# Brake_Light_Board_1.net
KiCad netlist of a schematic drawn in EAGLE
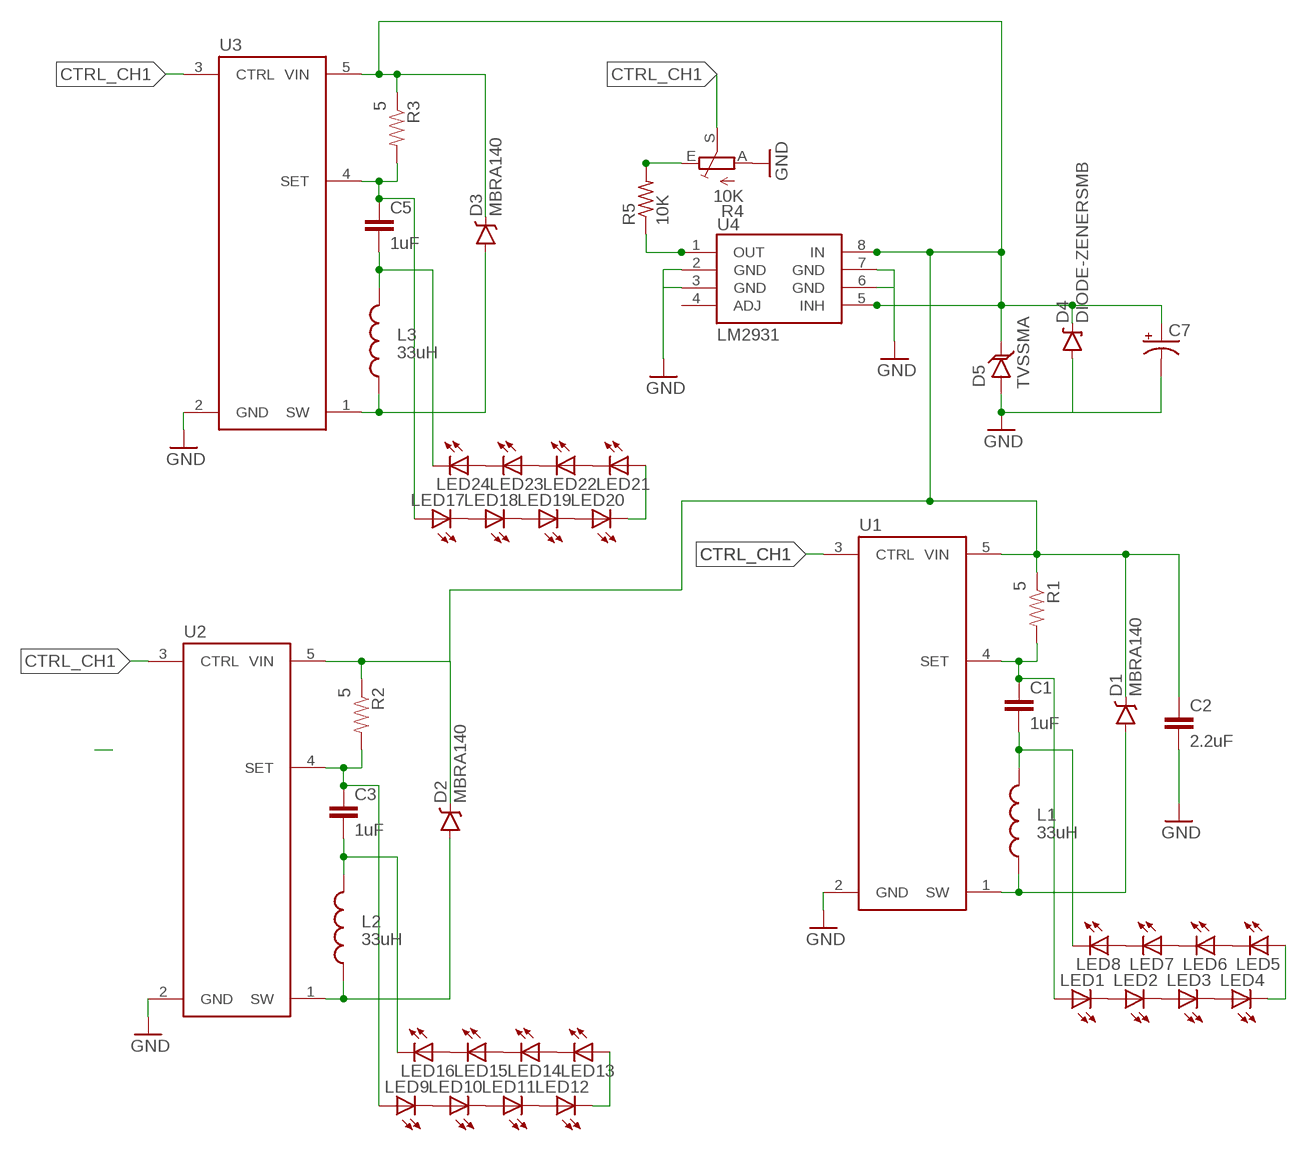
[diagram p0: schematic, sheet 1]

(export (version "E")
  (design (tool "Eeschema 10.0.6"))
  (components
    (comp (ref "C1")
      (value "1uF")
      (footprint "eagle-import:1206")
      (libsource (lib "eagle-import") (part "1.0UF50V10%(1206)"))
    )
    (comp (ref "C2")
      (value "2.2uF")
      (footprint "eagle-import:1206")
      (libsource (lib "eagle-import") (part "2.2UF50V10%(1206)"))
    )
    (comp (ref "C3")
      (value "1uF")
      (footprint "eagle-import:1206")
      (libsource (lib "eagle-import") (part "1.0UF50V10%(1206)"))
    )
    (comp (ref "C5")
      (value "1uF")
      (footprint "eagle-import:1206")
      (libsource (lib "eagle-import") (part "1.0UF50V10%(1206)"))
    )
    (comp (ref "C7")
      (value "CAP_POL6032")
      (footprint "eagle-import:EIA6032")
      (libsource (lib "eagle-import") (part "CAP_POL6032"))
    )
    (comp (ref "D1")
      (value "MBRA140")
      (footprint "eagle-import:SMA-DIODE")
      (libsource (lib "eagle-import") (part "DIODE-SCHOTTKY-MBRA140"))
    )
    (comp (ref "D2")
      (value "MBRA140")
      (footprint "eagle-import:SMA-DIODE")
      (libsource (lib "eagle-import") (part "DIODE-SCHOTTKY-MBRA140"))
    )
    (comp (ref "D3")
      (value "MBRA140")
      (footprint "eagle-import:SMA-DIODE")
      (libsource (lib "eagle-import") (part "DIODE-SCHOTTKY-MBRA140"))
    )
    (comp (ref "D4")
      (value "DIODE-ZENERSMB")
      (footprint "eagle-import:SMB-DIODE")
      (libsource (lib "eagle-import") (part "DIODE-ZENERSMB"))
    )
    (comp (ref "D5")
      (value "TVSSMA")
      (footprint "eagle-import:SMA-DIODE")
      (libsource (lib "eagle-import") (part "TVSSMA"))
    )
    (comp (ref "L1")
      (value "33uH")
      (footprint "eagle-import:SRN6045")
      (libsource (lib "eagle-import") (part "INDUCTORBOURNS_SRN6045"))
    )
    (comp (ref "L2")
      (value "33uH")
      (footprint "eagle-import:SRN6045")
      (libsource (lib "eagle-import") (part "INDUCTORBOURNS_SRN6045"))
    )
    (comp (ref "L3")
      (value "33uH")
      (footprint "eagle-import:SRN6045")
      (libsource (lib "eagle-import") (part "INDUCTORBOURNS_SRN6045"))
    )
    (comp (ref "LED1")
      (value "LED5MM")
      (footprint "eagle-import:LED5MM")
      (libsource (lib "eagle-import") (part "LED5MM"))
    )
    (comp (ref "LED2")
      (value "LED5MM")
      (footprint "eagle-import:LED5MM")
      (libsource (lib "eagle-import") (part "LED5MM"))
    )
    (comp (ref "LED3")
      (value "LED5MM")
      (footprint "eagle-import:LED5MM")
      (libsource (lib "eagle-import") (part "LED5MM"))
    )
    (comp (ref "LED4")
      (value "LED5MM")
      (footprint "eagle-import:LED5MM")
      (libsource (lib "eagle-import") (part "LED5MM"))
    )
    (comp (ref "LED5")
      (value "LED5MM")
      (footprint "eagle-import:LED5MM")
      (libsource (lib "eagle-import") (part "LED5MM"))
    )
    (comp (ref "LED6")
      (value "LED5MM")
      (footprint "eagle-import:LED5MM")
      (libsource (lib "eagle-import") (part "LED5MM"))
    )
    (comp (ref "LED7")
      (value "LED5MM")
      (footprint "eagle-import:LED5MM")
      (libsource (lib "eagle-import") (part "LED5MM"))
    )
    (comp (ref "LED8")
      (value "LED5MM")
      (footprint "eagle-import:LED5MM")
      (libsource (lib "eagle-import") (part "LED5MM"))
    )
    (comp (ref "LED9")
      (value "LED5MM")
      (footprint "eagle-import:LED5MM")
      (libsource (lib "eagle-import") (part "LED5MM"))
    )
    (comp (ref "LED10")
      (value "LED5MM")
      (footprint "eagle-import:LED5MM")
      (libsource (lib "eagle-import") (part "LED5MM"))
    )
    (comp (ref "LED11")
      (value "LED5MM")
      (footprint "eagle-import:LED5MM")
      (libsource (lib "eagle-import") (part "LED5MM"))
    )
    (comp (ref "LED12")
      (value "LED5MM")
      (footprint "eagle-import:LED5MM")
      (libsource (lib "eagle-import") (part "LED5MM"))
    )
    (comp (ref "LED13")
      (value "LED5MM")
      (footprint "eagle-import:LED5MM")
      (libsource (lib "eagle-import") (part "LED5MM"))
    )
    (comp (ref "LED14")
      (value "LED5MM")
      (footprint "eagle-import:LED5MM")
      (libsource (lib "eagle-import") (part "LED5MM"))
    )
    (comp (ref "LED15")
      (value "LED5MM")
      (footprint "eagle-import:LED5MM")
      (libsource (lib "eagle-import") (part "LED5MM"))
    )
    (comp (ref "LED16")
      (value "LED5MM")
      (footprint "eagle-import:LED5MM")
      (libsource (lib "eagle-import") (part "LED5MM"))
    )
    (comp (ref "LED17")
      (value "LED5MM")
      (footprint "eagle-import:LED5MM")
      (libsource (lib "eagle-import") (part "LED5MM"))
    )
    (comp (ref "LED18")
      (value "LED5MM")
      (footprint "eagle-import:LED5MM")
      (libsource (lib "eagle-import") (part "LED5MM"))
    )
    (comp (ref "LED19")
      (value "LED5MM")
      (footprint "eagle-import:LED5MM")
      (libsource (lib "eagle-import") (part "LED5MM"))
    )
    (comp (ref "LED20")
      (value "LED5MM")
      (footprint "eagle-import:LED5MM")
      (libsource (lib "eagle-import") (part "LED5MM"))
    )
    (comp (ref "LED21")
      (value "LED5MM")
      (footprint "eagle-import:LED5MM")
      (libsource (lib "eagle-import") (part "LED5MM"))
    )
    (comp (ref "LED22")
      (value "LED5MM")
      (footprint "eagle-import:LED5MM")
      (libsource (lib "eagle-import") (part "LED5MM"))
    )
    (comp (ref "LED23")
      (value "LED5MM")
      (footprint "eagle-import:LED5MM")
      (libsource (lib "eagle-import") (part "LED5MM"))
    )
    (comp (ref "LED24")
      (value "LED5MM")
      (footprint "eagle-import:LED5MM")
      (libsource (lib "eagle-import") (part "LED5MM"))
    )
    (comp (ref "R1")
      (value "5")
      (footprint "eagle-import:0805")
      (libsource (lib "eagle-import") (part "0.3OHM-1/8W-1%(0805)"))
    )
    (comp (ref "R2")
      (value "5")
      (footprint "eagle-import:0805")
      (libsource (lib "eagle-import") (part "0.3OHM-1/8W-1%(0805)"))
    )
    (comp (ref "R3")
      (value "5")
      (footprint "eagle-import:0805")
      (libsource (lib "eagle-import") (part "0.3OHM-1/8W-1%(0805)"))
    )
    (comp (ref "R4")
      (value "10K")
      (footprint "eagle-import:B25P")
      (libsource (lib "eagle-import") (part "TRIM_EU-B25P"))
    )
    (comp (ref "R5")
      (value "10K")
      (footprint "eagle-import:R0805")
      (libsource (lib "eagle-import") (part "R-US_R0805"))
    )
    (comp (ref "U1")
      (value "AL8805")
      (footprint "eagle-import:SOT23-5")
      (libsource (lib "eagle-import") (part "AL8805"))
    )
    (comp (ref "U2")
      (value "AL8805")
      (footprint "eagle-import:SOT23-5")
      (libsource (lib "eagle-import") (part "AL8805"))
    )
    (comp (ref "U3")
      (value "AL8805")
      (footprint "eagle-import:SOT23-5")
      (libsource (lib "eagle-import") (part "AL8805"))
    )
    (comp (ref "U4")
      (value "LM2931")
      (footprint "eagle-import:SO08")
      (libsource (lib "eagle-import") (part "LM2931"))
    )
  )
  (nets
    (net (code "1") (name "/OUT+1") (class "Default")
      (node (ref "C3") (pin "1") (pinfunction "1_1") (pintype "passive"))
      (node (ref "LED9") (pin "A") (pinfunction "A_A") (pintype "passive"))
      (node (ref "R2") (pin "2") (pinfunction "2_2") (pintype "passive"))
      (node (ref "U2") (pin "4") (pinfunction "SET_4") (pintype "bidirectional"))
    )
    (net (code "2") (name "CTRL_CH1") (class "Default")
      (node (ref "R4") (pin "S") (pinfunction "S_S") (pintype "passive"))
      (node (ref "U1") (pin "3") (pinfunction "CTRL_3") (pintype "bidirectional"))
      (node (ref "U2") (pin "3") (pinfunction "CTRL_3") (pintype "bidirectional"))
      (node (ref "U3") (pin "3") (pinfunction "CTRL_3") (pintype "bidirectional"))
    )
    (net (code "3") (name "GND") (class "Default")
      (node (ref "C2") (pin "2") (pinfunction "2_2") (pintype "passive"))
      (node (ref "C7") (pin "P$2") (pinfunction "-_P$2") (pintype "passive"))
      (node (ref "D4") (pin "A") (pinfunction "A_A") (pintype "passive"))
      (node (ref "D5") (pin "A") (pinfunction "A_A") (pintype "passive"))
      (node (ref "R4") (pin "A") (pinfunction "A_A") (pintype "passive"))
      (node (ref "U1") (pin "2") (pinfunction "GND_2") (pintype "bidirectional"))
      (node (ref "U2") (pin "2") (pinfunction "GND_2") (pintype "bidirectional"))
      (node (ref "U3") (pin "2") (pinfunction "GND_2") (pintype "bidirectional"))
      (node (ref "U4") (pin "2") (pinfunction "GND_2") (pintype "bidirectional"))
      (node (ref "U4") (pin "6") (pinfunction "GND_6") (pintype "bidirectional"))
      (node (ref "U4") (pin "7") (pinfunction "GND_7") (pintype "bidirectional"))
    )
    (net (code "4") (name "Net-(C7-+)") (class "Default")
      (node (ref "C2") (pin "1") (pinfunction "1_1") (pintype "passive"))
      (node (ref "C7") (pin "P$1") (pinfunction "+_P$1") (pintype "passive"))
      (node (ref "D1") (pin "C") (pinfunction "C_C") (pintype "passive"))
      (node (ref "D2") (pin "C") (pinfunction "C_C") (pintype "passive"))
      (node (ref "D3") (pin "C") (pinfunction "C_C") (pintype "passive"))
      (node (ref "D4") (pin "C") (pinfunction "C_C") (pintype "passive"))
      (node (ref "D5") (pin "C") (pinfunction "C_C") (pintype "passive"))
      (node (ref "R1") (pin "1") (pinfunction "1_1") (pintype "passive"))
      (node (ref "R2") (pin "1") (pinfunction "1_1") (pintype "passive"))
      (node (ref "R3") (pin "1") (pinfunction "1_1") (pintype "passive"))
      (node (ref "U1") (pin "5") (pinfunction "VIN_5") (pintype "bidirectional"))
      (node (ref "U2") (pin "5") (pinfunction "VIN_5") (pintype "bidirectional"))
      (node (ref "U3") (pin "5") (pinfunction "VIN_5") (pintype "bidirectional"))
      (node (ref "U4") (pin "5") (pinfunction "INH_5") (pintype "bidirectional"))
      (node (ref "U4") (pin "8") (pinfunction "IN_8") (pintype "bidirectional"))
    )
    (net (code "5") (name "Net-(LED1-C)") (class "Default")
      (node (ref "LED1") (pin "K") (pinfunction "C_K") (pintype "passive"))
      (node (ref "LED2") (pin "A") (pinfunction "A_A") (pintype "passive"))
    )
    (net (code "6") (name "Net-(LED2-C)") (class "Default")
      (node (ref "LED2") (pin "K") (pinfunction "C_K") (pintype "passive"))
      (node (ref "LED3") (pin "A") (pinfunction "A_A") (pintype "passive"))
    )
    (net (code "7") (name "Net-(LED3-C)") (class "Default")
      (node (ref "LED3") (pin "K") (pinfunction "C_K") (pintype "passive"))
      (node (ref "LED4") (pin "A") (pinfunction "A_A") (pintype "passive"))
    )
    (net (code "8") (name "Net-(LED4-C)") (class "Default")
      (node (ref "LED4") (pin "K") (pinfunction "C_K") (pintype "passive"))
      (node (ref "LED5") (pin "A") (pinfunction "A_A") (pintype "passive"))
    )
    (net (code "9") (name "Net-(LED5-C)") (class "Default")
      (node (ref "LED5") (pin "K") (pinfunction "C_K") (pintype "passive"))
      (node (ref "LED6") (pin "A") (pinfunction "A_A") (pintype "passive"))
    )
    (net (code "10") (name "Net-(LED6-C)") (class "Default")
      (node (ref "LED6") (pin "K") (pinfunction "C_K") (pintype "passive"))
      (node (ref "LED7") (pin "A") (pinfunction "A_A") (pintype "passive"))
    )
    (net (code "11") (name "Net-(LED7-C)") (class "Default")
      (node (ref "LED7") (pin "K") (pinfunction "C_K") (pintype "passive"))
      (node (ref "LED8") (pin "A") (pinfunction "A_A") (pintype "passive"))
    )
    (net (code "12") (name "Net-(LED8-C)") (class "Default")
      (node (ref "C1") (pin "2") (pinfunction "2_2") (pintype "passive"))
      (node (ref "L1") (pin "2") (pinfunction "2_2") (pintype "passive"))
      (node (ref "LED8") (pin "K") (pinfunction "C_K") (pintype "passive"))
    )
    (net (code "13") (name "Net-(LED9-C)") (class "Default")
      (node (ref "LED10") (pin "A") (pinfunction "A_A") (pintype "passive"))
      (node (ref "LED9") (pin "K") (pinfunction "C_K") (pintype "passive"))
    )
    (net (code "14") (name "Net-(LED10-C)") (class "Default")
      (node (ref "LED10") (pin "K") (pinfunction "C_K") (pintype "passive"))
      (node (ref "LED11") (pin "A") (pinfunction "A_A") (pintype "passive"))
    )
    (net (code "15") (name "Net-(LED11-C)") (class "Default")
      (node (ref "LED11") (pin "K") (pinfunction "C_K") (pintype "passive"))
      (node (ref "LED12") (pin "A") (pinfunction "A_A") (pintype "passive"))
    )
    (net (code "16") (name "Net-(LED12-C)") (class "Default")
      (node (ref "LED12") (pin "K") (pinfunction "C_K") (pintype "passive"))
      (node (ref "LED13") (pin "A") (pinfunction "A_A") (pintype "passive"))
    )
    (net (code "17") (name "Net-(LED13-C)") (class "Default")
      (node (ref "LED13") (pin "K") (pinfunction "C_K") (pintype "passive"))
      (node (ref "LED14") (pin "A") (pinfunction "A_A") (pintype "passive"))
    )
    (net (code "18") (name "Net-(LED14-C)") (class "Default")
      (node (ref "LED14") (pin "K") (pinfunction "C_K") (pintype "passive"))
      (node (ref "LED15") (pin "A") (pinfunction "A_A") (pintype "passive"))
    )
    (net (code "19") (name "Net-(LED15-C)") (class "Default")
      (node (ref "LED15") (pin "K") (pinfunction "C_K") (pintype "passive"))
      (node (ref "LED16") (pin "A") (pinfunction "A_A") (pintype "passive"))
    )
    (net (code "20") (name "Net-(LED16-C)") (class "Default")
      (node (ref "C3") (pin "2") (pinfunction "2_2") (pintype "passive"))
      (node (ref "L2") (pin "2") (pinfunction "2_2") (pintype "passive"))
      (node (ref "LED16") (pin "K") (pinfunction "C_K") (pintype "passive"))
    )
    (net (code "21") (name "Net-(LED17-C)") (class "Default")
      (node (ref "LED17") (pin "K") (pinfunction "C_K") (pintype "passive"))
      (node (ref "LED18") (pin "A") (pinfunction "A_A") (pintype "passive"))
    )
    (net (code "22") (name "Net-(LED18-C)") (class "Default")
      (node (ref "LED18") (pin "K") (pinfunction "C_K") (pintype "passive"))
      (node (ref "LED19") (pin "A") (pinfunction "A_A") (pintype "passive"))
    )
    (net (code "23") (name "Net-(LED19-C)") (class "Default")
      (node (ref "LED19") (pin "K") (pinfunction "C_K") (pintype "passive"))
      (node (ref "LED20") (pin "A") (pinfunction "A_A") (pintype "passive"))
    )
    (net (code "24") (name "Net-(LED20-C)") (class "Default")
      (node (ref "LED20") (pin "K") (pinfunction "C_K") (pintype "passive"))
      (node (ref "LED21") (pin "A") (pinfunction "A_A") (pintype "passive"))
    )
    (net (code "25") (name "Net-(LED21-C)") (class "Default")
      (node (ref "LED21") (pin "K") (pinfunction "C_K") (pintype "passive"))
      (node (ref "LED22") (pin "A") (pinfunction "A_A") (pintype "passive"))
    )
    (net (code "26") (name "Net-(LED22-C)") (class "Default")
      (node (ref "LED22") (pin "K") (pinfunction "C_K") (pintype "passive"))
      (node (ref "LED23") (pin "A") (pinfunction "A_A") (pintype "passive"))
    )
    (net (code "27") (name "Net-(LED23-C)") (class "Default")
      (node (ref "LED23") (pin "K") (pinfunction "C_K") (pintype "passive"))
      (node (ref "LED24") (pin "A") (pinfunction "A_A") (pintype "passive"))
    )
    (net (code "28") (name "Net-(LED24-C)") (class "Default")
      (node (ref "C5") (pin "2") (pinfunction "2_2") (pintype "passive"))
      (node (ref "L3") (pin "2") (pinfunction "2_2") (pintype "passive"))
      (node (ref "LED24") (pin "K") (pinfunction "C_K") (pintype "passive"))
    )
    (net (code "29") (name "Net-(R4-PadE)") (class "Default")
      (node (ref "R4") (pin "E") (pinfunction "E_E") (pintype "passive"))
      (node (ref "R5") (pin "2") (pinfunction "2_2") (pintype "passive"))
    )
    (net (code "30") (name "Net-(U1-SET)") (class "Default")
      (node (ref "C1") (pin "1") (pinfunction "1_1") (pintype "passive"))
      (node (ref "LED1") (pin "A") (pinfunction "A_A") (pintype "passive"))
      (node (ref "R1") (pin "2") (pinfunction "2_2") (pintype "passive"))
      (node (ref "U1") (pin "4") (pinfunction "SET_4") (pintype "bidirectional"))
    )
    (net (code "31") (name "Net-(U1-SW)") (class "Default")
      (node (ref "D1") (pin "A") (pinfunction "A_A") (pintype "passive"))
      (node (ref "L1") (pin "1") (pinfunction "1_1") (pintype "passive"))
      (node (ref "U1") (pin "1") (pinfunction "SW_1") (pintype "bidirectional"))
    )
    (net (code "32") (name "Net-(U2-SW)") (class "Default")
      (node (ref "D2") (pin "A") (pinfunction "A_A") (pintype "passive"))
      (node (ref "L2") (pin "1") (pinfunction "1_1") (pintype "passive"))
      (node (ref "U2") (pin "1") (pinfunction "SW_1") (pintype "bidirectional"))
    )
    (net (code "33") (name "Net-(U3-SET)") (class "Default")
      (node (ref "C5") (pin "1") (pinfunction "1_1") (pintype "passive"))
      (node (ref "LED17") (pin "A") (pinfunction "A_A") (pintype "passive"))
      (node (ref "R3") (pin "2") (pinfunction "2_2") (pintype "passive"))
      (node (ref "U3") (pin "4") (pinfunction "SET_4") (pintype "bidirectional"))
    )
    (net (code "34") (name "Net-(U3-SW)") (class "Default")
      (node (ref "D3") (pin "A") (pinfunction "A_A") (pintype "passive"))
      (node (ref "L3") (pin "1") (pinfunction "1_1") (pintype "passive"))
      (node (ref "U3") (pin "1") (pinfunction "SW_1") (pintype "bidirectional"))
    )
    (net (code "35") (name "Net-(U4-OUT)") (class "Default")
      (node (ref "R5") (pin "1") (pinfunction "1_1") (pintype "passive"))
      (node (ref "U4") (pin "1") (pinfunction "OUT_1") (pintype "bidirectional"))
    )
    (net (code "36") (name "unconnected-(U4-ADJ-Pad4)") (class "Default")
      (node (ref "U4") (pin "4") (pinfunction "ADJ_4") (pintype "bidirectional"))
    )
    (net (code "37") (name "unconnected-(U4-GND-Pad3)") (class "Default")
      (node (ref "U4") (pin "3") (pinfunction "GND_3") (pintype "bidirectional"))
    )
  )
)
